# BaseCard.net
KiCad netlist of a schematic drawn in Altium Designer
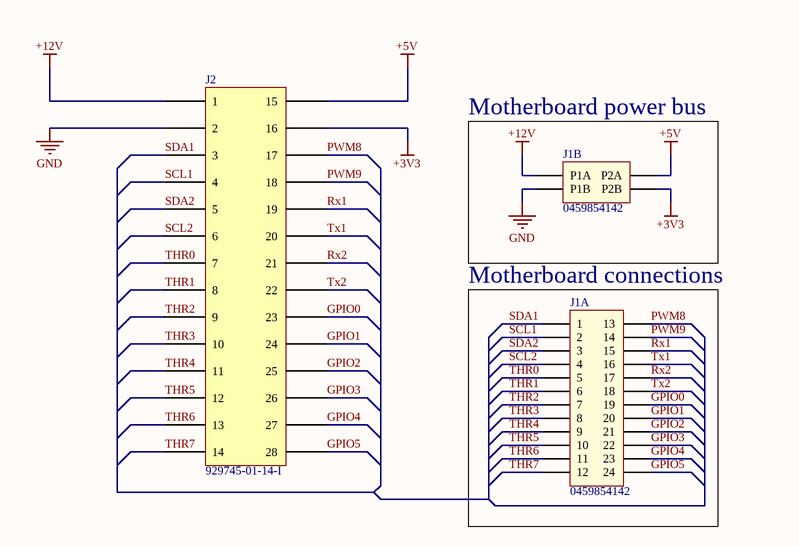
[diagram p0: BaseCard.SchDoc]

(export (version "E")
  (design (tool "Eeschema 10.0.6"))
  (components
    (comp (ref "J1")
      (value "0459854142")
      (footprint "CONN_HEADER_4PWR_24SGL_2.36MM")
      (libsource (lib "Vortex-component-database") (part "LPHPower_connector"))
    )
    (comp (ref "J2")
      (value "929745-01-14-I")
      (footprint "Header_14x2_RA")
      (libsource (lib "Vortex-component-database") (part "Header 14x2 RA"))
    )
  )
  (nets
    (net (code "1") (name "+3V3") (class "Default")
      (node (ref "J1") (pin "P2B") (pinfunction "P2B_P2B") (pintype "passive"))
      (node (ref "J2") (pin "16") (pinfunction "16_16") (pintype "passive"))
    )
    (net (code "2") (name "+5V") (class "Default")
      (node (ref "J1") (pin "P2A") (pinfunction "P2A_P2A") (pintype "passive"))
      (node (ref "J2") (pin "15") (pinfunction "15_15") (pintype "passive"))
    )
    (net (code "3") (name "+12V") (class "Default")
      (node (ref "J1") (pin "P1A") (pinfunction "P1A_P1A") (pintype "passive"))
      (node (ref "J2") (pin "1") (pinfunction "1_1") (pintype "passive"))
    )
    (net (code "4") (name "/GPIO0") (class "Default")
      (node (ref "J1") (pin "19") (pinfunction "19_19") (pintype "passive"))
      (node (ref "J2") (pin "23") (pinfunction "23_23") (pintype "passive"))
    )
    (net (code "5") (name "/GPIO1") (class "Default")
      (node (ref "J1") (pin "20") (pinfunction "20_20") (pintype "passive"))
      (node (ref "J2") (pin "24") (pinfunction "24_24") (pintype "passive"))
    )
    (net (code "6") (name "/GPIO2") (class "Default")
      (node (ref "J1") (pin "21") (pinfunction "21_21") (pintype "passive"))
      (node (ref "J2") (pin "25") (pinfunction "25_25") (pintype "passive"))
    )
    (net (code "7") (name "/GPIO3") (class "Default")
      (node (ref "J1") (pin "22") (pinfunction "22_22") (pintype "passive"))
      (node (ref "J2") (pin "26") (pinfunction "26_26") (pintype "passive"))
    )
    (net (code "8") (name "/GPIO4") (class "Default")
      (node (ref "J1") (pin "23") (pinfunction "23_23") (pintype "passive"))
      (node (ref "J2") (pin "27") (pinfunction "27_27") (pintype "passive"))
    )
    (net (code "9") (name "/GPIO5") (class "Default")
      (node (ref "J1") (pin "24") (pinfunction "24_24") (pintype "passive"))
      (node (ref "J2") (pin "28") (pinfunction "28_28") (pintype "passive"))
    )
    (net (code "10") (name "/PWM8") (class "Default")
      (node (ref "J1") (pin "13") (pinfunction "13_13") (pintype "passive"))
      (node (ref "J2") (pin "17") (pinfunction "17_17") (pintype "passive"))
    )
    (net (code "11") (name "/PWM9") (class "Default")
      (node (ref "J1") (pin "14") (pinfunction "14_14") (pintype "passive"))
      (node (ref "J2") (pin "18") (pinfunction "18_18") (pintype "passive"))
    )
    (net (code "12") (name "/Rx1") (class "Default")
      (node (ref "J1") (pin "15") (pinfunction "15_15") (pintype "passive"))
      (node (ref "J2") (pin "19") (pinfunction "19_19") (pintype "passive"))
    )
    (net (code "13") (name "/Rx2") (class "Default")
      (node (ref "J1") (pin "17") (pinfunction "17_17") (pintype "passive"))
      (node (ref "J2") (pin "21") (pinfunction "21_21") (pintype "passive"))
    )
    (net (code "14") (name "/SCL1") (class "Default")
      (node (ref "J1") (pin "2") (pinfunction "2_2") (pintype "passive"))
      (node (ref "J2") (pin "4") (pinfunction "4_4") (pintype "passive"))
    )
    (net (code "15") (name "/SCL2") (class "Default")
      (node (ref "J1") (pin "4") (pinfunction "4_4") (pintype "passive"))
      (node (ref "J2") (pin "6") (pinfunction "6_6") (pintype "passive"))
    )
    (net (code "16") (name "/SDA1") (class "Default")
      (node (ref "J1") (pin "1") (pinfunction "1_1") (pintype "passive"))
      (node (ref "J2") (pin "3") (pinfunction "3_3") (pintype "passive"))
    )
    (net (code "17") (name "/SDA2") (class "Default")
      (node (ref "J1") (pin "3") (pinfunction "3_3") (pintype "passive"))
      (node (ref "J2") (pin "5") (pinfunction "5_5") (pintype "passive"))
    )
    (net (code "18") (name "/THR0") (class "Default")
      (node (ref "J1") (pin "5") (pinfunction "5_5") (pintype "passive"))
      (node (ref "J2") (pin "7") (pinfunction "7_7") (pintype "passive"))
    )
    (net (code "19") (name "/THR1") (class "Default")
      (node (ref "J1") (pin "6") (pinfunction "6_6") (pintype "passive"))
      (node (ref "J2") (pin "8") (pinfunction "8_8") (pintype "passive"))
    )
    (net (code "20") (name "/THR2") (class "Default")
      (node (ref "J1") (pin "7") (pinfunction "7_7") (pintype "passive"))
      (node (ref "J2") (pin "9") (pinfunction "9_9") (pintype "passive"))
    )
    (net (code "21") (name "/THR3") (class "Default")
      (node (ref "J1") (pin "8") (pinfunction "8_8") (pintype "passive"))
      (node (ref "J2") (pin "10") (pinfunction "10_10") (pintype "passive"))
    )
    (net (code "22") (name "/THR4") (class "Default")
      (node (ref "J1") (pin "9") (pinfunction "9_9") (pintype "passive"))
      (node (ref "J2") (pin "11") (pinfunction "11_11") (pintype "passive"))
    )
    (net (code "23") (name "/THR5") (class "Default")
      (node (ref "J1") (pin "10") (pinfunction "10_10") (pintype "passive"))
      (node (ref "J2") (pin "12") (pinfunction "12_12") (pintype "passive"))
    )
    (net (code "24") (name "/THR6") (class "Default")
      (node (ref "J1") (pin "11") (pinfunction "11_11") (pintype "passive"))
      (node (ref "J2") (pin "13") (pinfunction "13_13") (pintype "passive"))
    )
    (net (code "25") (name "/THR7") (class "Default")
      (node (ref "J1") (pin "12") (pinfunction "12_12") (pintype "passive"))
      (node (ref "J2") (pin "14") (pinfunction "14_14") (pintype "passive"))
    )
    (net (code "26") (name "/Tx1") (class "Default")
      (node (ref "J1") (pin "16") (pinfunction "16_16") (pintype "passive"))
      (node (ref "J2") (pin "20") (pinfunction "20_20") (pintype "passive"))
    )
    (net (code "27") (name "/Tx2") (class "Default")
      (node (ref "J1") (pin "18") (pinfunction "18_18") (pintype "passive"))
      (node (ref "J2") (pin "22") (pinfunction "22_22") (pintype "passive"))
    )
    (net (code "28") (name "GND") (class "Default")
      (node (ref "J1") (pin "P1B") (pinfunction "P1B_P1B") (pintype "passive"))
      (node (ref "J2") (pin "2") (pinfunction "2_2") (pintype "passive"))
    )
  )
)
